# witch-transfer1.net
KiCad netlist of a schematic drawn in EAGLE
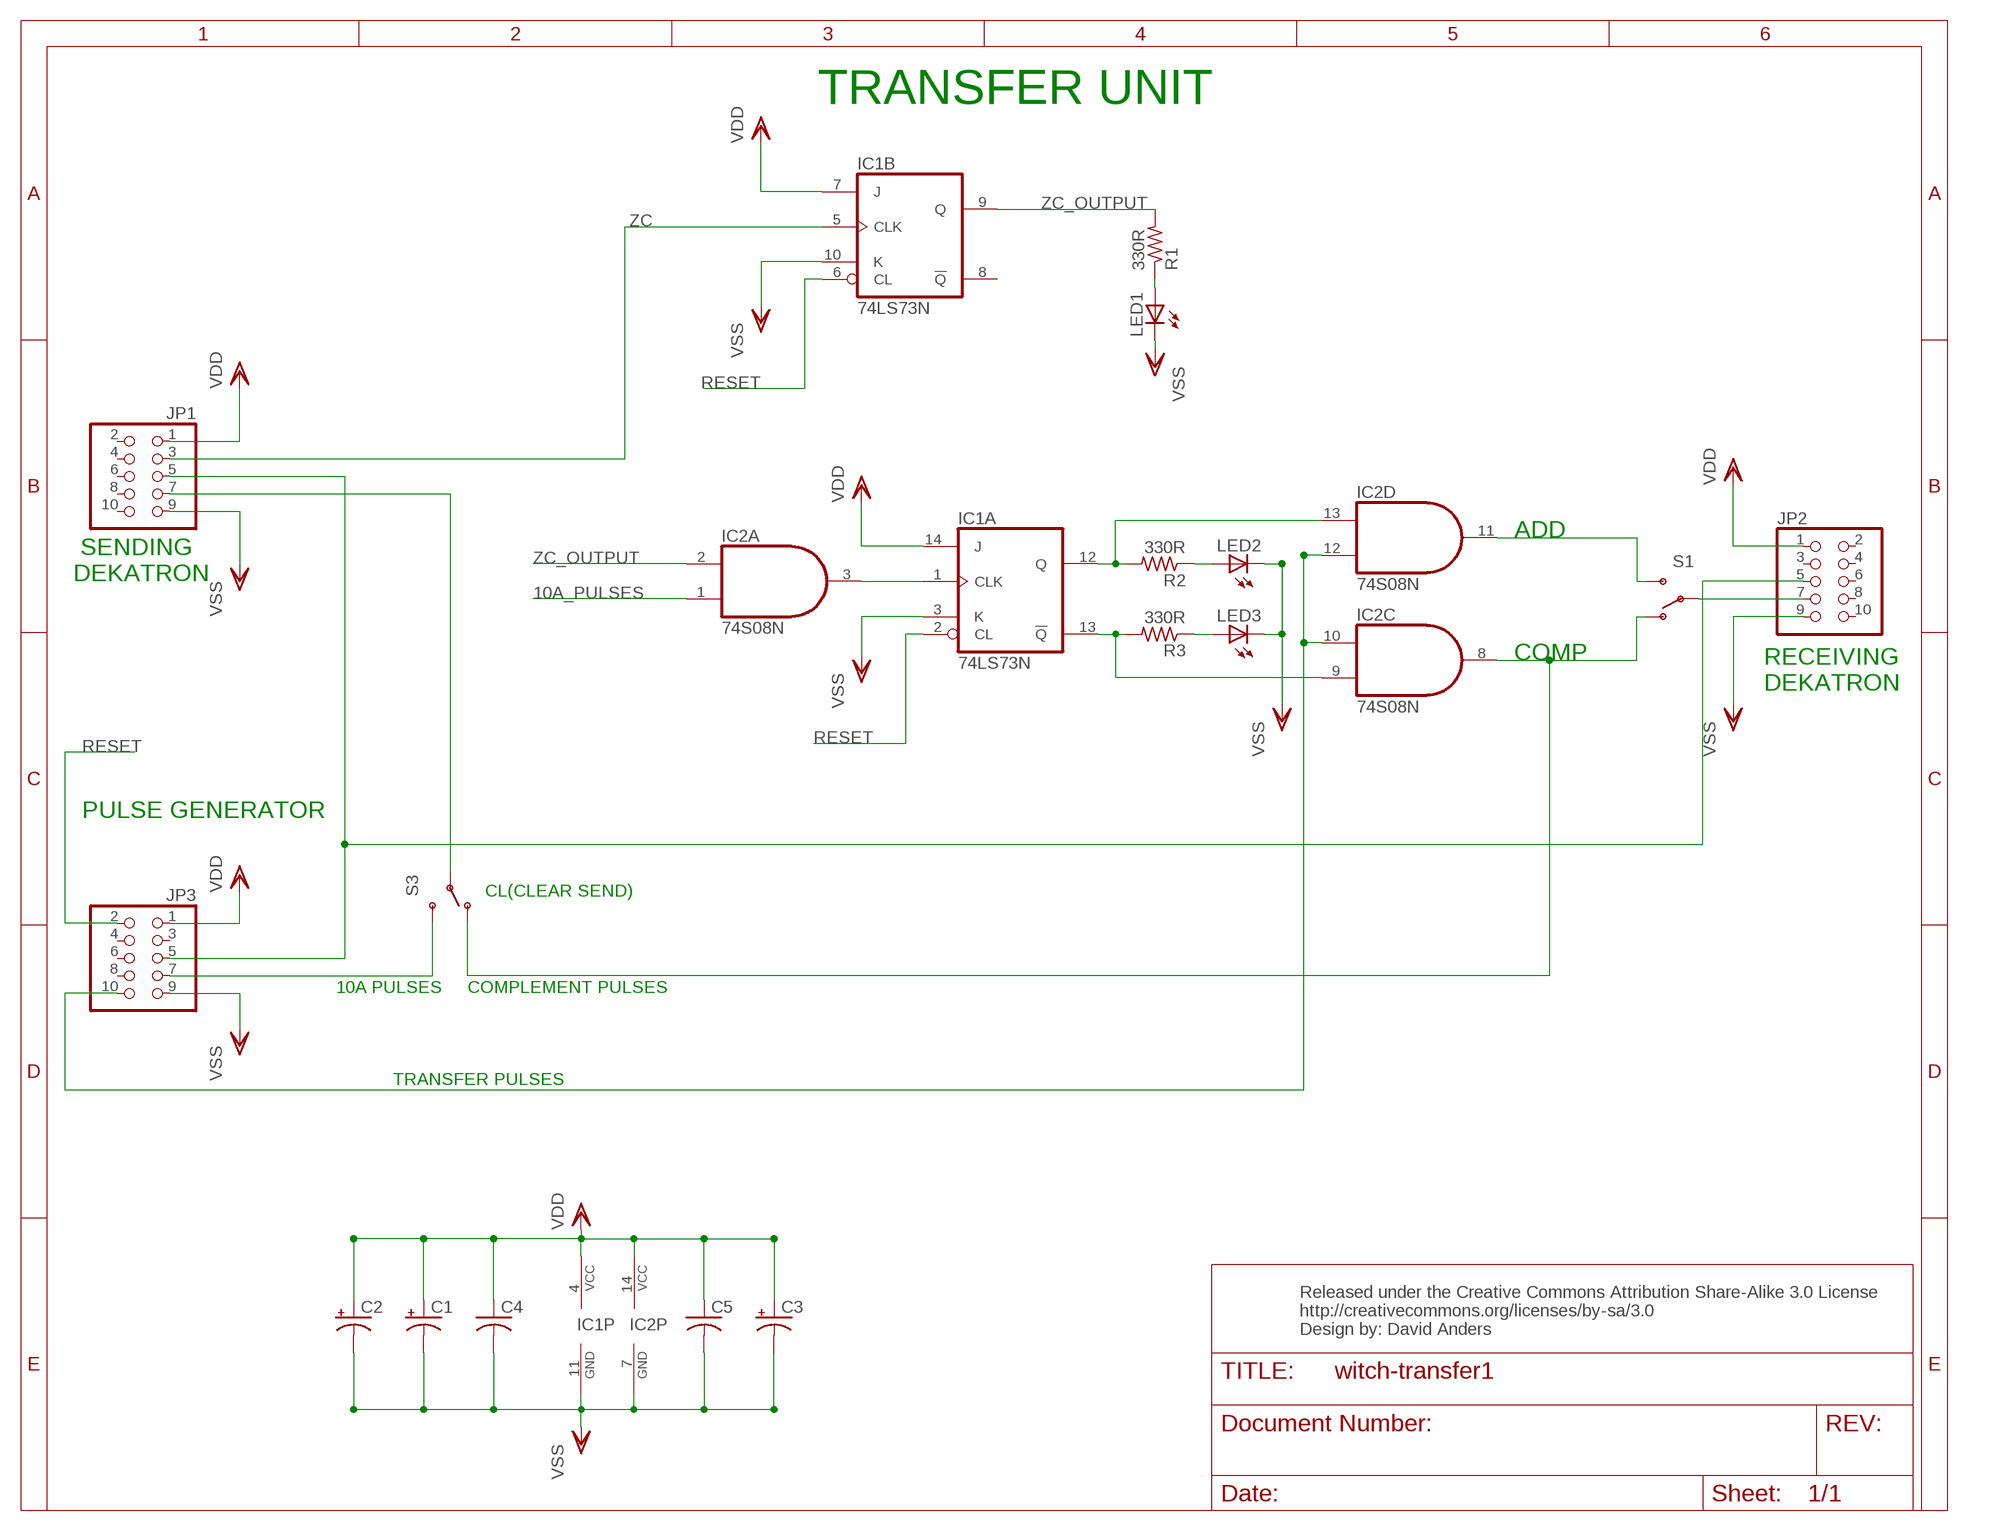
[diagram p0: schematic, sheet 1]

(export (version "E")
  (design (tool "Eeschema 10.0.6"))
  (components
    (comp (ref "C1")
      (value "CPOL-USE2-5")
      (footprint "eagle-import:E2-5")
      (libsource (lib "eagle-import") (part "CPOL-USE2-5"))
    )
    (comp (ref "C2")
      (value "CPOL-USE2-5")
      (footprint "eagle-import:E2-5")
      (libsource (lib "eagle-import") (part "CPOL-USE2-5"))
    )
    (comp (ref "C3")
      (value "CPOL-USE2-5")
      (footprint "eagle-import:E2-5")
      (libsource (lib "eagle-import") (part "CPOL-USE2-5"))
    )
    (comp (ref "C4")
      (value "C-US025-025X050")
      (footprint "eagle-import:C025-025X050")
      (libsource (lib "eagle-import") (part "C-US025-025X050"))
    )
    (comp (ref "C5")
      (value "C-US025-025X050")
      (footprint "eagle-import:C025-025X050")
      (libsource (lib "eagle-import") (part "C-US025-025X050"))
    )
    (comp (ref "IC1")
      (value "74LS73N")
      (footprint "eagle-import:DIL14")
      (libsource (lib "eagle-import") (part "7473NLS"))
    )
    (comp (ref "IC2")
      (value "74S08N")
      (footprint "eagle-import:DIL14")
      (libsource (lib "eagle-import") (part "7408NS"))
    )
    (comp (ref "JP1")
      (value "PINHD-2X5")
      (footprint "eagle-import:2X05")
      (libsource (lib "eagle-import") (part "PINHD-2X5"))
    )
    (comp (ref "JP2")
      (value "PINHD-2X5")
      (footprint "eagle-import:2X05")
      (libsource (lib "eagle-import") (part "PINHD-2X5"))
    )
    (comp (ref "JP3")
      (value "PINHD-2X5")
      (footprint "eagle-import:2X05")
      (libsource (lib "eagle-import") (part "PINHD-2X5"))
    )
    (comp (ref "LED1")
      (value "LED5MM")
      (footprint "eagle-import:LED5MM")
      (libsource (lib "eagle-import") (part "LED5MM"))
    )
    (comp (ref "LED2")
      (value "LED5MM")
      (footprint "eagle-import:LED5MM")
      (libsource (lib "eagle-import") (part "LED5MM"))
    )
    (comp (ref "LED3")
      (value "LED5MM")
      (footprint "eagle-import:LED5MM")
      (libsource (lib "eagle-import") (part "LED5MM"))
    )
    (comp (ref "R1")
      (value "330R")
      (footprint "eagle-import:0204_5")
      (libsource (lib "eagle-import") (part "R-US_0204/5"))
    )
    (comp (ref "R2")
      (value "330R")
      (footprint "eagle-import:0204_5")
      (libsource (lib "eagle-import") (part "R-US_0204/5"))
    )
    (comp (ref "R3")
      (value "330R")
      (footprint "eagle-import:0204_5")
      (libsource (lib "eagle-import") (part "R-US_0204/5"))
    )
    (comp (ref "S1")
      (value "SWITCH-SPDTPTH")
      (footprint "eagle-import:SWITCH-SPDT")
      (libsource (lib "eagle-import") (part "SWITCH-SPDTPTH"))
    )
    (comp (ref "S3")
      (value "SWITCH-SPDTPTH")
      (footprint "eagle-import:SWITCH-SPDT")
      (libsource (lib "eagle-import") (part "SWITCH-SPDTPTH"))
    )
  )
  (nets
    (net (code "1") (name "/10A_PULSES") (class "Default")
      (node (ref "IC2") (pin "1") (pinfunction "I0_1") (pintype "input"))
      (node (ref "JP3") (pin "7") (pinfunction "7_7") (pintype "passive"))
      (node (ref "S3") (pin "3") (pinfunction "S_3") (pintype "passive"))
    )
    (net (code "2") (name "/RESET") (class "Default")
      (node (ref "IC1") (pin "2") (pinfunction "CL_2") (pintype "input"))
      (node (ref "IC1") (pin "6") (pinfunction "CL_6") (pintype "input"))
      (node (ref "JP3") (pin "2") (pinfunction "2_2") (pintype "passive"))
    )
    (net (code "3") (name "/ZC") (class "Default")
      (node (ref "IC1") (pin "5") (pinfunction "CLK_5") (pintype "input"))
      (node (ref "JP1") (pin "3") (pinfunction "3_3") (pintype "passive"))
    )
    (net (code "4") (name "/ZC_OUTPUT") (class "Default")
      (node (ref "IC1") (pin "9") (pinfunction "Q_9") (pintype "output"))
      (node (ref "IC2") (pin "2") (pinfunction "I1_2") (pintype "input"))
      (node (ref "R1") (pin "2") (pinfunction "2_2") (pintype "passive"))
    )
    (net (code "5") (name "Net-(IC1A-CLK)") (class "Default")
      (node (ref "IC1") (pin "1") (pinfunction "CLK_1") (pintype "input"))
      (node (ref "IC2") (pin "3") (pinfunction "O_3") (pintype "output"))
    )
    (net (code "6") (name "Net-(IC1A-Q)") (class "Default")
      (node (ref "IC1") (pin "12") (pinfunction "Q_12") (pintype "output"))
      (node (ref "IC2") (pin "13") (pinfunction "I1_13") (pintype "input"))
      (node (ref "R2") (pin "2") (pinfunction "2_2") (pintype "passive"))
    )
    (net (code "7") (name "Net-(IC1A-~{Q})") (class "Default")
      (node (ref "IC1") (pin "13") (pinfunction "~{Q}_13") (pintype "output"))
      (node (ref "IC2") (pin "9") (pinfunction "I0_9") (pintype "input"))
      (node (ref "R3") (pin "2") (pinfunction "2_2") (pintype "passive"))
    )
    (net (code "8") (name "Net-(IC2C-I1)") (class "Default")
      (node (ref "IC2") (pin "10") (pinfunction "I1_10") (pintype "input"))
      (node (ref "IC2") (pin "12") (pinfunction "I0_12") (pintype "input"))
      (node (ref "JP3") (pin "10") (pinfunction "10_10") (pintype "passive"))
    )
    (net (code "9") (name "Net-(IC2C-O)") (class "Default")
      (node (ref "IC2") (pin "8") (pinfunction "O_8") (pintype "output"))
      (node (ref "S1") (pin "1") (pinfunction "O_1") (pintype "passive"))
      (node (ref "S3") (pin "1") (pinfunction "O_1") (pintype "passive"))
    )
    (net (code "10") (name "Net-(IC2D-O)") (class "Default")
      (node (ref "IC2") (pin "11") (pinfunction "O_11") (pintype "output"))
      (node (ref "S1") (pin "3") (pinfunction "S_3") (pintype "passive"))
    )
    (net (code "11") (name "Net-(JP1-Pad5)") (class "Default")
      (node (ref "JP1") (pin "5") (pinfunction "5_5") (pintype "passive"))
      (node (ref "JP2") (pin "5") (pinfunction "5_5") (pintype "passive"))
      (node (ref "JP3") (pin "5") (pinfunction "5_5") (pintype "passive"))
    )
    (net (code "12") (name "Net-(LED1-PadA)") (class "Default")
      (node (ref "LED1") (pin "A") (pinfunction "A_A") (pintype "passive"))
      (node (ref "R1") (pin "1") (pinfunction "1_1") (pintype "passive"))
    )
    (net (code "13") (name "Net-(LED2-PadA)") (class "Default")
      (node (ref "LED2") (pin "A") (pinfunction "A_A") (pintype "passive"))
      (node (ref "R2") (pin "1") (pinfunction "1_1") (pintype "passive"))
    )
    (net (code "14") (name "Net-(LED3-PadA)") (class "Default")
      (node (ref "LED3") (pin "A") (pinfunction "A_A") (pintype "passive"))
      (node (ref "R3") (pin "1") (pinfunction "1_1") (pintype "passive"))
    )
    (net (code "15") (name "Net-(S1-P)") (class "Default")
      (node (ref "JP2") (pin "7") (pinfunction "7_7") (pintype "passive"))
      (node (ref "S1") (pin "2") (pinfunction "P_2") (pintype "passive"))
    )
    (net (code "16") (name "Net-(S3-P)") (class "Default")
      (node (ref "JP1") (pin "7") (pinfunction "7_7") (pintype "passive"))
      (node (ref "S3") (pin "2") (pinfunction "P_2") (pintype "passive"))
    )
    (net (code "17") (name "VDD") (class "Default")
      (node (ref "C1") (pin "+") (pinfunction "+_+") (pintype "passive"))
      (node (ref "C2") (pin "+") (pinfunction "+_+") (pintype "passive"))
      (node (ref "C3") (pin "+") (pinfunction "+_+") (pintype "passive"))
      (node (ref "C4") (pin "1") (pinfunction "1_1") (pintype "passive"))
      (node (ref "C5") (pin "1") (pinfunction "1_1") (pintype "passive"))
      (node (ref "IC1") (pin "14") (pinfunction "J_14") (pintype "input"))
      (node (ref "IC1") (pin "4") (pinfunction "VCC_4") (pintype "power_in"))
      (node (ref "IC1") (pin "7") (pinfunction "J_7") (pintype "input"))
      (node (ref "IC2") (pin "14") (pinfunction "VCC_14") (pintype "power_in"))
      (node (ref "JP1") (pin "1") (pinfunction "1_1") (pintype "passive"))
      (node (ref "JP2") (pin "1") (pinfunction "1_1") (pintype "passive"))
      (node (ref "JP3") (pin "1") (pinfunction "1_1") (pintype "passive"))
    )
    (net (code "18") (name "VSS") (class "Default")
      (node (ref "C1") (pin "-") (pinfunction "-_-") (pintype "passive"))
      (node (ref "C2") (pin "-") (pinfunction "-_-") (pintype "passive"))
      (node (ref "C3") (pin "-") (pinfunction "-_-") (pintype "passive"))
      (node (ref "C4") (pin "2") (pinfunction "2_2") (pintype "passive"))
      (node (ref "C5") (pin "2") (pinfunction "2_2") (pintype "passive"))
      (node (ref "IC1") (pin "10") (pinfunction "K_10") (pintype "input"))
      (node (ref "IC1") (pin "11") (pinfunction "GND_11") (pintype "power_in"))
      (node (ref "IC1") (pin "3") (pinfunction "K_3") (pintype "input"))
      (node (ref "IC2") (pin "7") (pinfunction "GND_7") (pintype "power_in"))
      (node (ref "JP1") (pin "9") (pinfunction "9_9") (pintype "passive"))
      (node (ref "JP2") (pin "9") (pinfunction "9_9") (pintype "passive"))
      (node (ref "JP3") (pin "9") (pinfunction "9_9") (pintype "passive"))
      (node (ref "LED1") (pin "K") (pinfunction "C_K") (pintype "passive"))
      (node (ref "LED2") (pin "K") (pinfunction "C_K") (pintype "passive"))
      (node (ref "LED3") (pin "K") (pinfunction "C_K") (pintype "passive"))
    )
    (net (code "19") (name "unconnected-(IC1B-~{Q}-Pad8)") (class "Default")
      (node (ref "IC1") (pin "8") (pinfunction "~{Q}_8") (pintype "output"))
    )
    (net (code "20") (name "unconnected-(JP1-Pad2)") (class "Default")
      (node (ref "JP1") (pin "2") (pinfunction "2_2") (pintype "passive"))
    )
    (net (code "21") (name "unconnected-(JP1-Pad4)") (class "Default")
      (node (ref "JP1") (pin "4") (pinfunction "4_4") (pintype "passive"))
    )
    (net (code "22") (name "unconnected-(JP1-Pad6)") (class "Default")
      (node (ref "JP1") (pin "6") (pinfunction "6_6") (pintype "passive"))
    )
    (net (code "23") (name "unconnected-(JP1-Pad8)") (class "Default")
      (node (ref "JP1") (pin "8") (pinfunction "8_8") (pintype "passive"))
    )
    (net (code "24") (name "unconnected-(JP1-Pad10)") (class "Default")
      (node (ref "JP1") (pin "10") (pinfunction "10_10") (pintype "passive"))
    )
    (net (code "25") (name "unconnected-(JP2-Pad2)") (class "Default")
      (node (ref "JP2") (pin "2") (pinfunction "2_2") (pintype "passive"))
    )
    (net (code "26") (name "unconnected-(JP2-Pad3)") (class "Default")
      (node (ref "JP2") (pin "3") (pinfunction "3_3") (pintype "passive"))
    )
    (net (code "27") (name "unconnected-(JP2-Pad4)") (class "Default")
      (node (ref "JP2") (pin "4") (pinfunction "4_4") (pintype "passive"))
    )
    (net (code "28") (name "unconnected-(JP2-Pad6)") (class "Default")
      (node (ref "JP2") (pin "6") (pinfunction "6_6") (pintype "passive"))
    )
    (net (code "29") (name "unconnected-(JP2-Pad8)") (class "Default")
      (node (ref "JP2") (pin "8") (pinfunction "8_8") (pintype "passive"))
    )
    (net (code "30") (name "unconnected-(JP2-Pad10)") (class "Default")
      (node (ref "JP2") (pin "10") (pinfunction "10_10") (pintype "passive"))
    )
    (net (code "31") (name "unconnected-(JP3-Pad3)") (class "Default")
      (node (ref "JP3") (pin "3") (pinfunction "3_3") (pintype "passive"))
    )
    (net (code "32") (name "unconnected-(JP3-Pad4)") (class "Default")
      (node (ref "JP3") (pin "4") (pinfunction "4_4") (pintype "passive"))
    )
    (net (code "33") (name "unconnected-(JP3-Pad6)") (class "Default")
      (node (ref "JP3") (pin "6") (pinfunction "6_6") (pintype "passive"))
    )
    (net (code "34") (name "unconnected-(JP3-Pad8)") (class "Default")
      (node (ref "JP3") (pin "8") (pinfunction "8_8") (pintype "passive"))
    )
  )
)
